# untitled.net
KiCad netlist of a schematic drawn in EAGLE
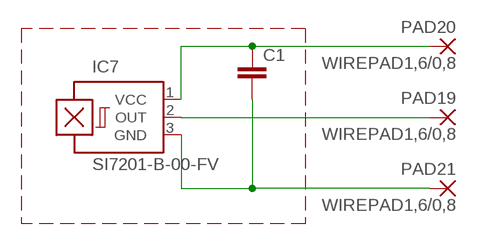
[diagram p0: schematic, sheet 1]

(export (version "E")
  (design (tool "Eeschema 10.0.6"))
  (components
    (comp (ref "C1")
      (value "C-EUC0402")
      (footprint "eagle-import:C0402")
      (libsource (lib "eagle-import") (part "C-EUC0402"))
    )
    (comp (ref "IC7")
      (value "SI7201-B-00-FV")
      (footprint "eagle-import:SOT23-W")
      (libsource (lib "eagle-import") (part "A12?LH02"))
    )
    (comp (ref "PAD19")
      (value "WIREPAD1,6/0,8")
      (footprint "eagle-import:1,6_0,8")
      (libsource (lib "eagle-import") (part "WIREPAD1,6/0,8"))
    )
    (comp (ref "PAD20")
      (value "WIREPAD1,6/0,8")
      (footprint "eagle-import:1,6_0,8")
      (libsource (lib "eagle-import") (part "WIREPAD1,6/0,8"))
    )
    (comp (ref "PAD21")
      (value "WIREPAD1,6/0,8")
      (footprint "eagle-import:1,6_0,8")
      (libsource (lib "eagle-import") (part "WIREPAD1,6/0,8"))
    )
  )
  (nets
    (net (code "1") (name "Net-(IC7-GND)") (class "Default")
      (node (ref "C1") (pin "2") (pinfunction "2_2") (pintype "passive"))
      (node (ref "IC7") (pin "3") (pinfunction "GND_3") (pintype "power_in"))
      (node (ref "PAD21") (pin "1") (pinfunction "P_1") (pintype "passive"))
    )
    (net (code "2") (name "Net-(IC7-OUT)") (class "Default")
      (node (ref "IC7") (pin "2") (pinfunction "OUT_2") (pintype "output"))
      (node (ref "PAD19") (pin "1") (pinfunction "P_1") (pintype "passive"))
    )
    (net (code "3") (name "Net-(IC7-VCC)") (class "Default")
      (node (ref "C1") (pin "1") (pinfunction "1_1") (pintype "passive"))
      (node (ref "IC7") (pin "1") (pinfunction "VCC_1") (pintype "power_in"))
      (node (ref "PAD20") (pin "1") (pinfunction "P_1") (pintype "passive"))
    )
  )
)
